# SCH_LED-CIRCUIT_2025-07-21.net
KiCad netlist of a schematic drawn in EasyEDA
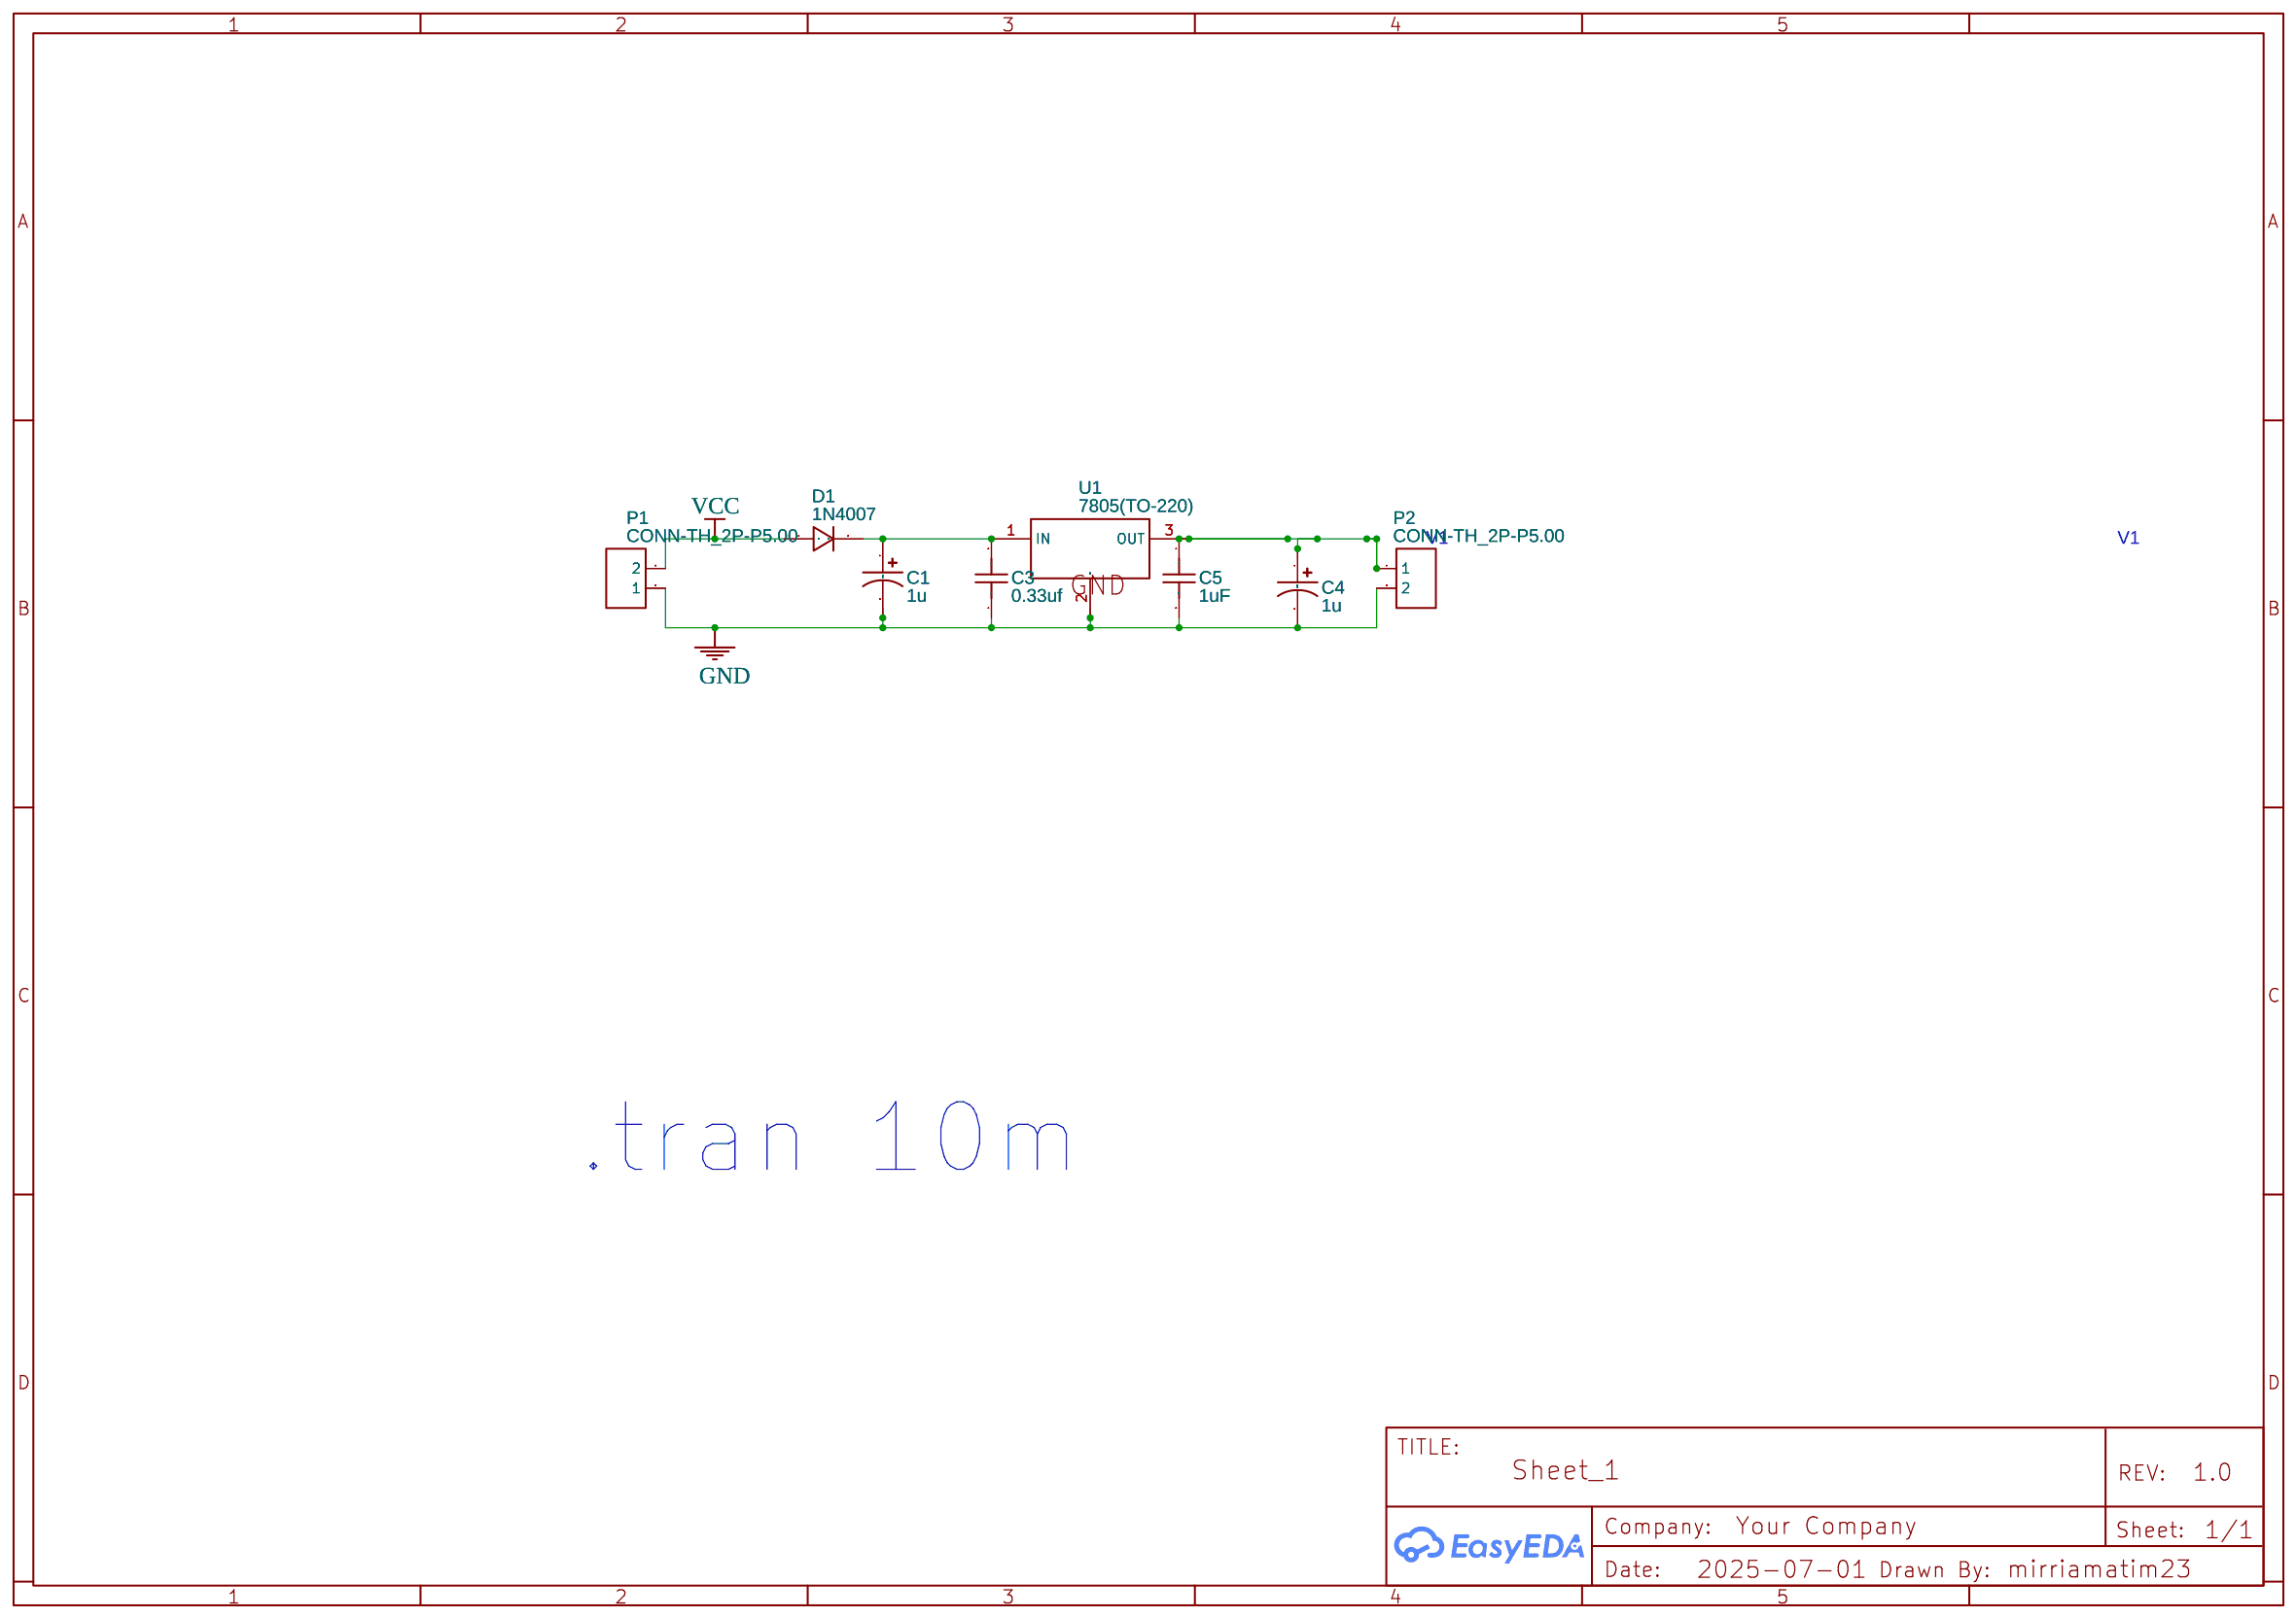
[diagram p0: schematic sheet]

(export (version "E")
  (design (tool "Eeschema 10.0.6"))
  (components
    (comp (ref "C1") (value "1u") (libsource (lib "") (part "CE_TH_D3.0×F1.5_US")))
    (comp (ref "C3") (value "0.33uf") (libsource (lib "") (part "C_RAD-0.1_US")))
    (comp (ref "C4") (value "1u") (libsource (lib "") (part "CE_TH_D3.0×F1.5_US")))
    (comp (ref "C5") (value "1uF") (libsource (lib "") (part "C_RAD-0.1_US_1")))
    (comp (ref "D1")
      (value "1N4007")
      (fields (field (name "Manufacturer") "SEMTECH"))
      (libsource (lib "") (part "1N4007"))
    )
    (comp (ref "P1") (value "CONN-TH_2P-P5.00") (libsource (lib "") (part "CONN-TH_2P-P5.00")))
    (comp (ref "P2") (value "CONN-TH_2P-P5.00") (libsource (lib "") (part "CONN-TH_2P-P5.00_1")))
    (comp (ref "U1")
      (value "7805(TO-220)")
      (fields
        (field (name "Manufacturer Part") "L7805CV-DG")
        (field (name "Manufacturer") "STMicroelectronics")
      )
      (libsource (lib "") (part "7805(TO-220)"))
    )
  )
  (nets
    (net (code "1") (name "GND") (class "Default")
      (node (ref "C1") (pin "2") (pinfunction "2_2") (pintype "unspecified"))
      (node (ref "C3") (pin "1") (pinfunction "1_1") (pintype "unspecified"))
      (node (ref "C4") (pin "2") (pinfunction "2_2") (pintype "unspecified"))
      (node (ref "C5") (pin "2") (pinfunction "2_2") (pintype "unspecified"))
      (node (ref "P1") (pin "1") (pinfunction "1_1") (pintype "unspecified"))
      (node (ref "P2") (pin "2") (pinfunction "2_2") (pintype "unspecified"))
      (node (ref "U1") (pin "2") (pinfunction "GND_2") (pintype "passive"))
    )
    (net (code "2") (name "Net-(U1-IN)") (class "Default")
      (node (ref "C1") (pin "1") (pinfunction "1_1") (pintype "unspecified"))
      (node (ref "C3") (pin "2") (pinfunction "2_2") (pintype "unspecified"))
      (node (ref "D1") (pin "1") (pinfunction "1_1") (pintype "unspecified"))
      (node (ref "U1") (pin "1") (pinfunction "IN_1") (pintype "passive"))
    )
    (net (code "3") (name "Net-(U1-OUT)") (class "Default")
      (node (ref "C4") (pin "1") (pinfunction "1_1") (pintype "unspecified"))
      (node (ref "C5") (pin "1") (pinfunction "1_1") (pintype "unspecified"))
      (node (ref "P2") (pin "1") (pinfunction "1_1") (pintype "unspecified"))
      (node (ref "U1") (pin "3") (pinfunction "OUT_3") (pintype "passive"))
    )
    (net (code "4") (name "VCC") (class "Default")
      (node (ref "D1") (pin "2") (pinfunction "2_2") (pintype "unspecified"))
      (node (ref "P1") (pin "2") (pinfunction "2_2") (pintype "unspecified"))
    )
  )
)
